# SCH_sine-wave-generator_2024-02-24.net
KiCad netlist of a schematic drawn in EasyEDA
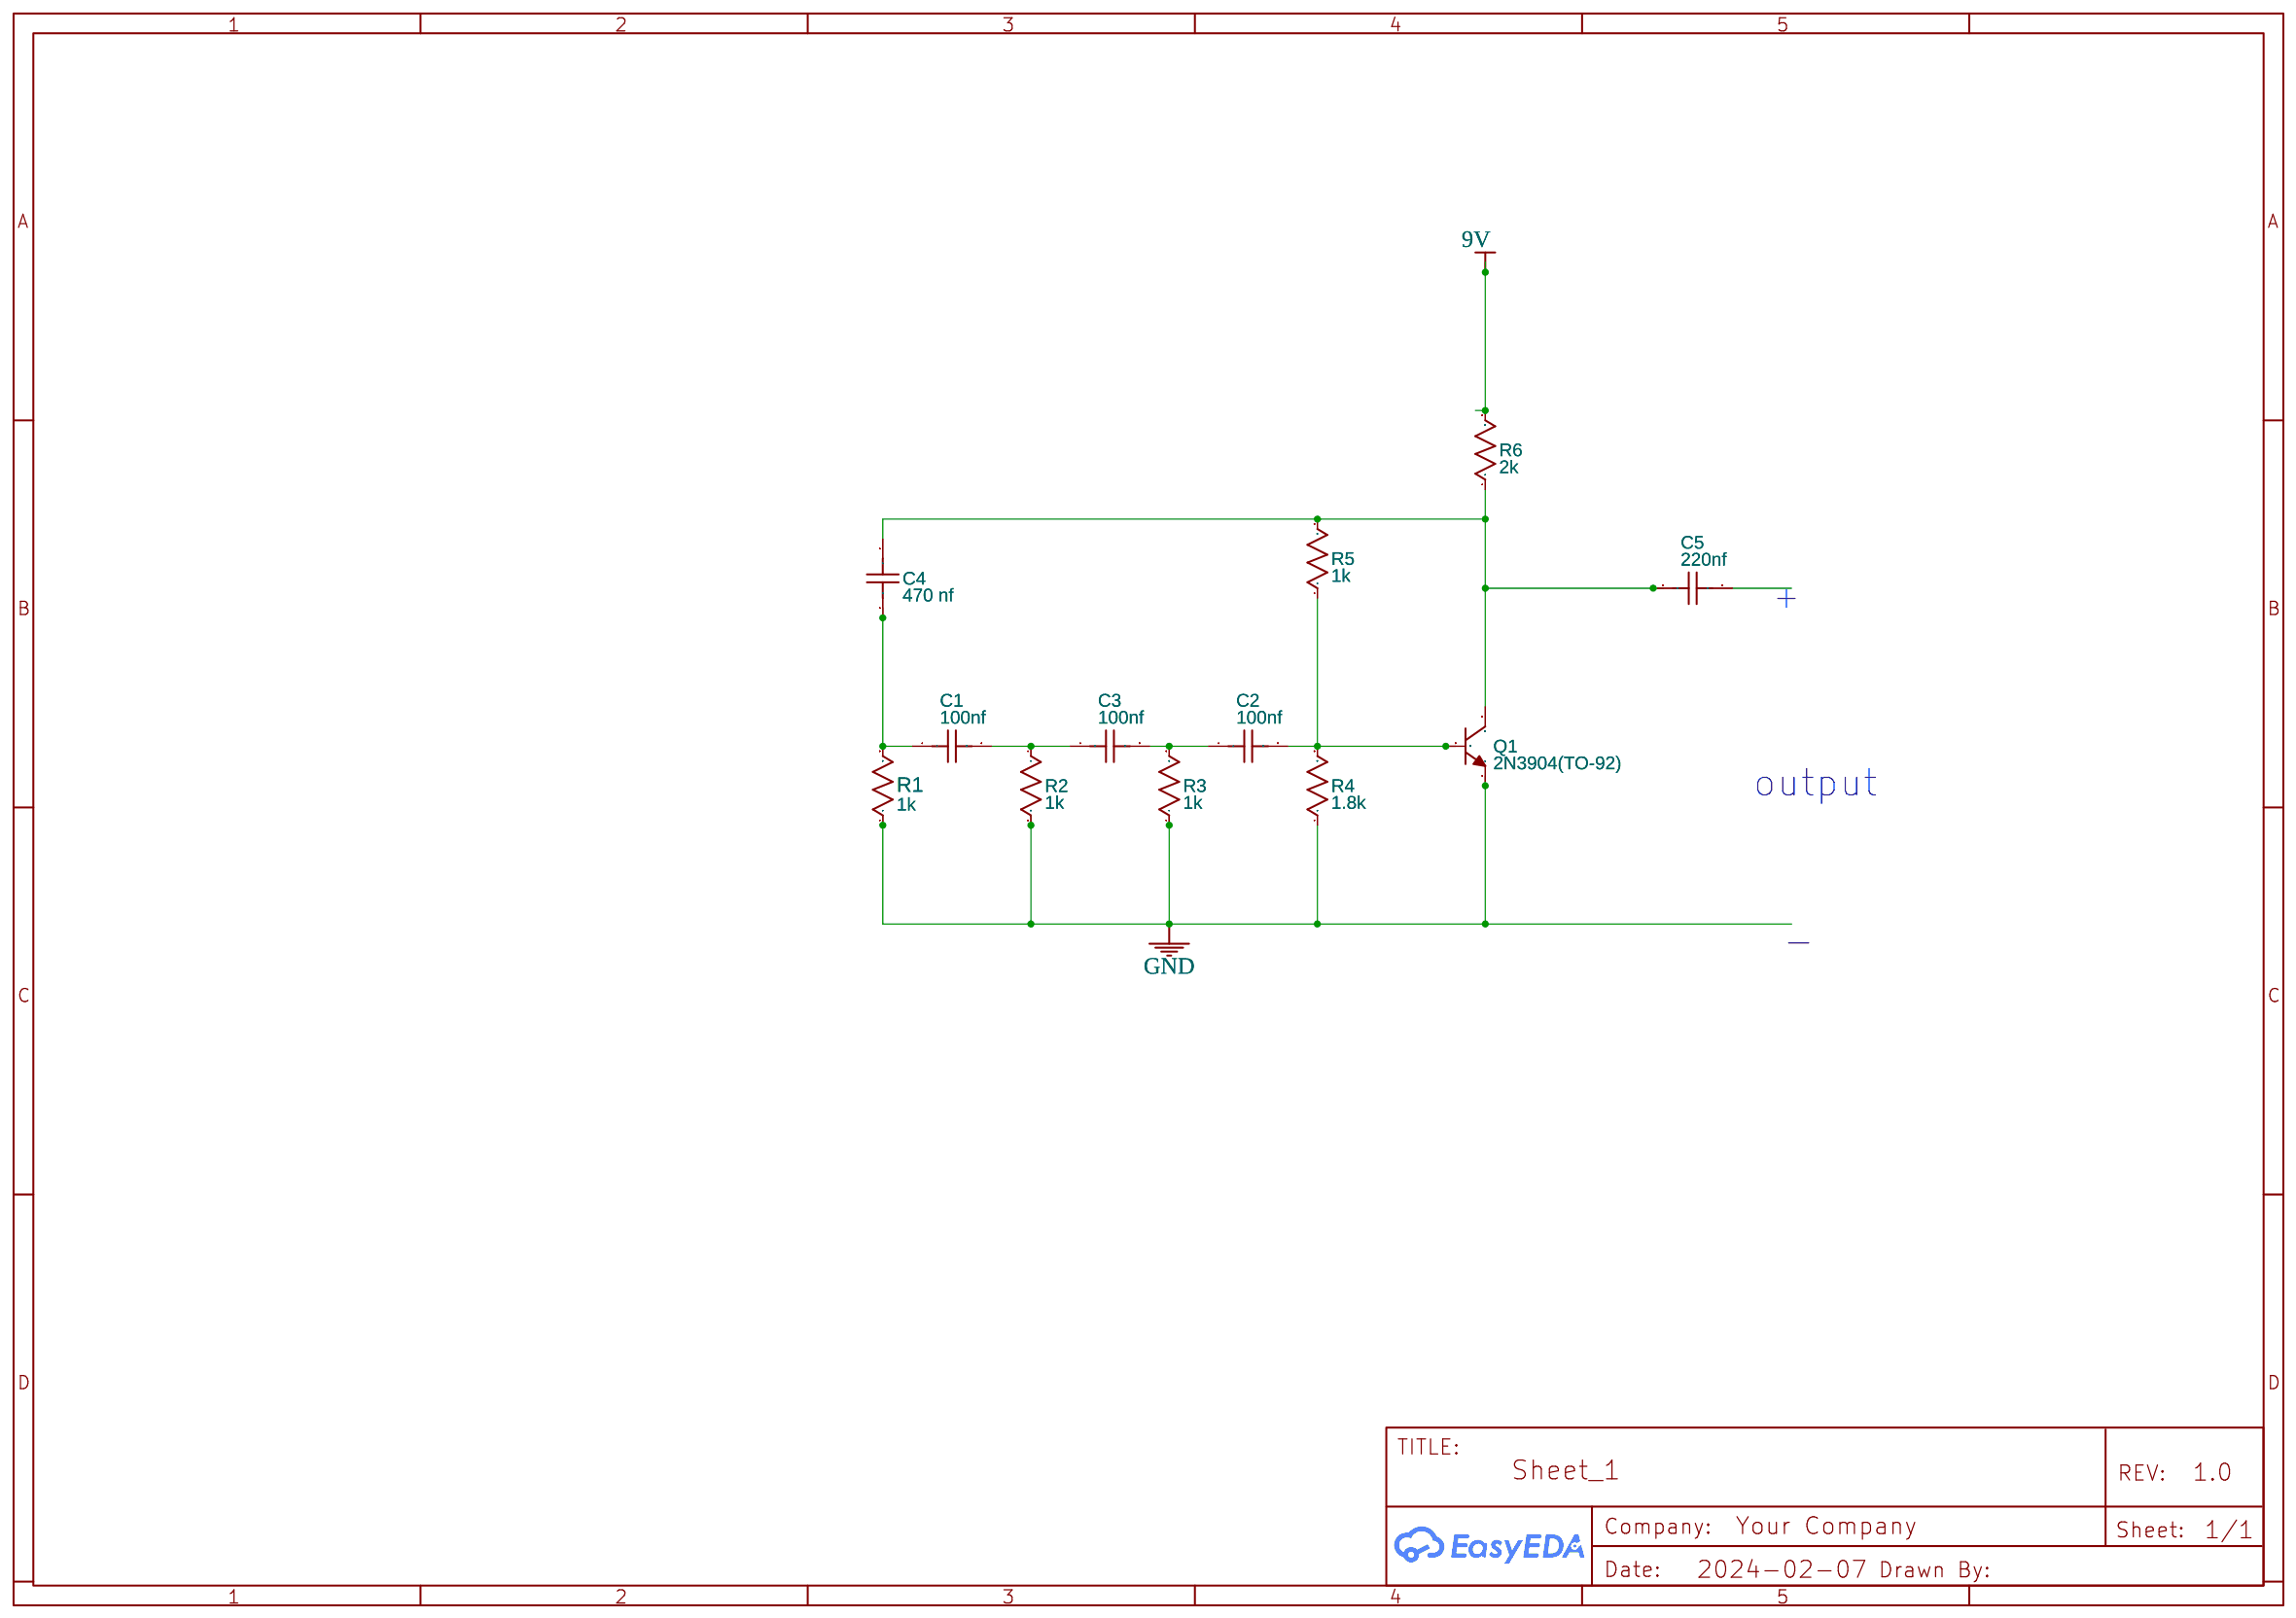
[diagram p0: schematic sheet]

(export (version "E")
  (design (tool "Eeschema 10.0.6"))
  (components
    (comp (ref "C1") (value "100nf") (libsource (lib "") (part "C_0603_US")))
    (comp (ref "C2") (value "100nf") (libsource (lib "") (part "C_0603_US")))
    (comp (ref "C3") (value "100nf") (libsource (lib "") (part "C_0603_US")))
    (comp (ref "C4") (value "470 nf") (libsource (lib "") (part "C_0603_US_2")))
    (comp (ref "C5") (value "220nf") (libsource (lib "") (part "C_0603_US_1")))
    (comp (ref "Q1")
      (value "2N3904(TO-92)")
      (fields (field (name "Manufacturer Part") "2N3904") (field (name "Manufacturer") "SEMTECH"))
      (libsource (lib "") (part "2N3904(TO-92)"))
    )
    (comp (ref "R1") (value "1k") (libsource (lib "") (part "R_0603_US_1")))
    (comp (ref "R2") (value "1k") (libsource (lib "") (part "R_0603_US")))
    (comp (ref "R3") (value "1k") (libsource (lib "") (part "R_0603_US_1")))
    (comp (ref "R4") (value "1.8k") (libsource (lib "") (part "R_0603_US_1")))
    (comp (ref "R5") (value "1k") (libsource (lib "") (part "R_0603_US_1")))
    (comp (ref "R6") (value "2k") (libsource (lib "") (part "R_0603_US_1")))
  )
  (nets
    (net (code "1") (name "9V") (class "Default")
      (node (ref "R6") (pin "2") (pinfunction "2_2") (pintype "unspecified"))
    )
    (net (code "2") (name "GND") (class "Default")
      (node (ref "Q1") (pin "1") (pinfunction "E_1") (pintype "unspecified"))
      (node (ref "R1") (pin "1") (pinfunction "1_1") (pintype "unspecified"))
      (node (ref "R2") (pin "2") (pinfunction "2_2") (pintype "unspecified"))
      (node (ref "R3") (pin "1") (pinfunction "1_1") (pintype "unspecified"))
      (node (ref "R4") (pin "1") (pinfunction "1_1") (pintype "unspecified"))
    )
    (net (code "3") (name "Net-(C1-Pad1)") (class "Default")
      (node (ref "C1") (pin "1") (pinfunction "1_1") (pintype "unspecified"))
      (node (ref "C4") (pin "1") (pinfunction "1_1") (pintype "unspecified"))
      (node (ref "R1") (pin "2") (pinfunction "2_2") (pintype "unspecified"))
    )
    (net (code "4") (name "Net-(C1-Pad2)") (class "Default")
      (node (ref "C1") (pin "2") (pinfunction "2_2") (pintype "unspecified"))
      (node (ref "C3") (pin "1") (pinfunction "1_1") (pintype "unspecified"))
      (node (ref "R2") (pin "1") (pinfunction "1_1") (pintype "unspecified"))
    )
    (net (code "5") (name "Net-(C2-Pad1)") (class "Default")
      (node (ref "C2") (pin "1") (pinfunction "1_1") (pintype "unspecified"))
      (node (ref "C3") (pin "2") (pinfunction "2_2") (pintype "unspecified"))
      (node (ref "R3") (pin "2") (pinfunction "2_2") (pintype "unspecified"))
    )
    (net (code "6") (name "Net-(Q1-B)") (class "Default")
      (node (ref "C2") (pin "2") (pinfunction "2_2") (pintype "unspecified"))
      (node (ref "Q1") (pin "2") (pinfunction "B_2") (pintype "unspecified"))
      (node (ref "R4") (pin "2") (pinfunction "2_2") (pintype "unspecified"))
      (node (ref "R5") (pin "1") (pinfunction "1_1") (pintype "unspecified"))
    )
    (net (code "7") (name "Net-(Q1-C)") (class "Default")
      (node (ref "C4") (pin "2") (pinfunction "2_2") (pintype "unspecified"))
      (node (ref "C5") (pin "2") (pinfunction "2_2") (pintype "unspecified"))
      (node (ref "Q1") (pin "3") (pinfunction "C_3") (pintype "unspecified"))
      (node (ref "R5") (pin "2") (pinfunction "2_2") (pintype "unspecified"))
      (node (ref "R6") (pin "1") (pinfunction "1_1") (pintype "unspecified"))
    )
    (net (code "8") (name "unconnected-(C5-Pad1)") (class "Default")
      (node (ref "C5") (pin "1") (pinfunction "1_1") (pintype "unspecified"))
    )
  )
)
